# ProPrj_Rak11310v3b_2025-04-18.net
KiCad netlist of a schematic drawn in EasyEDA Pro
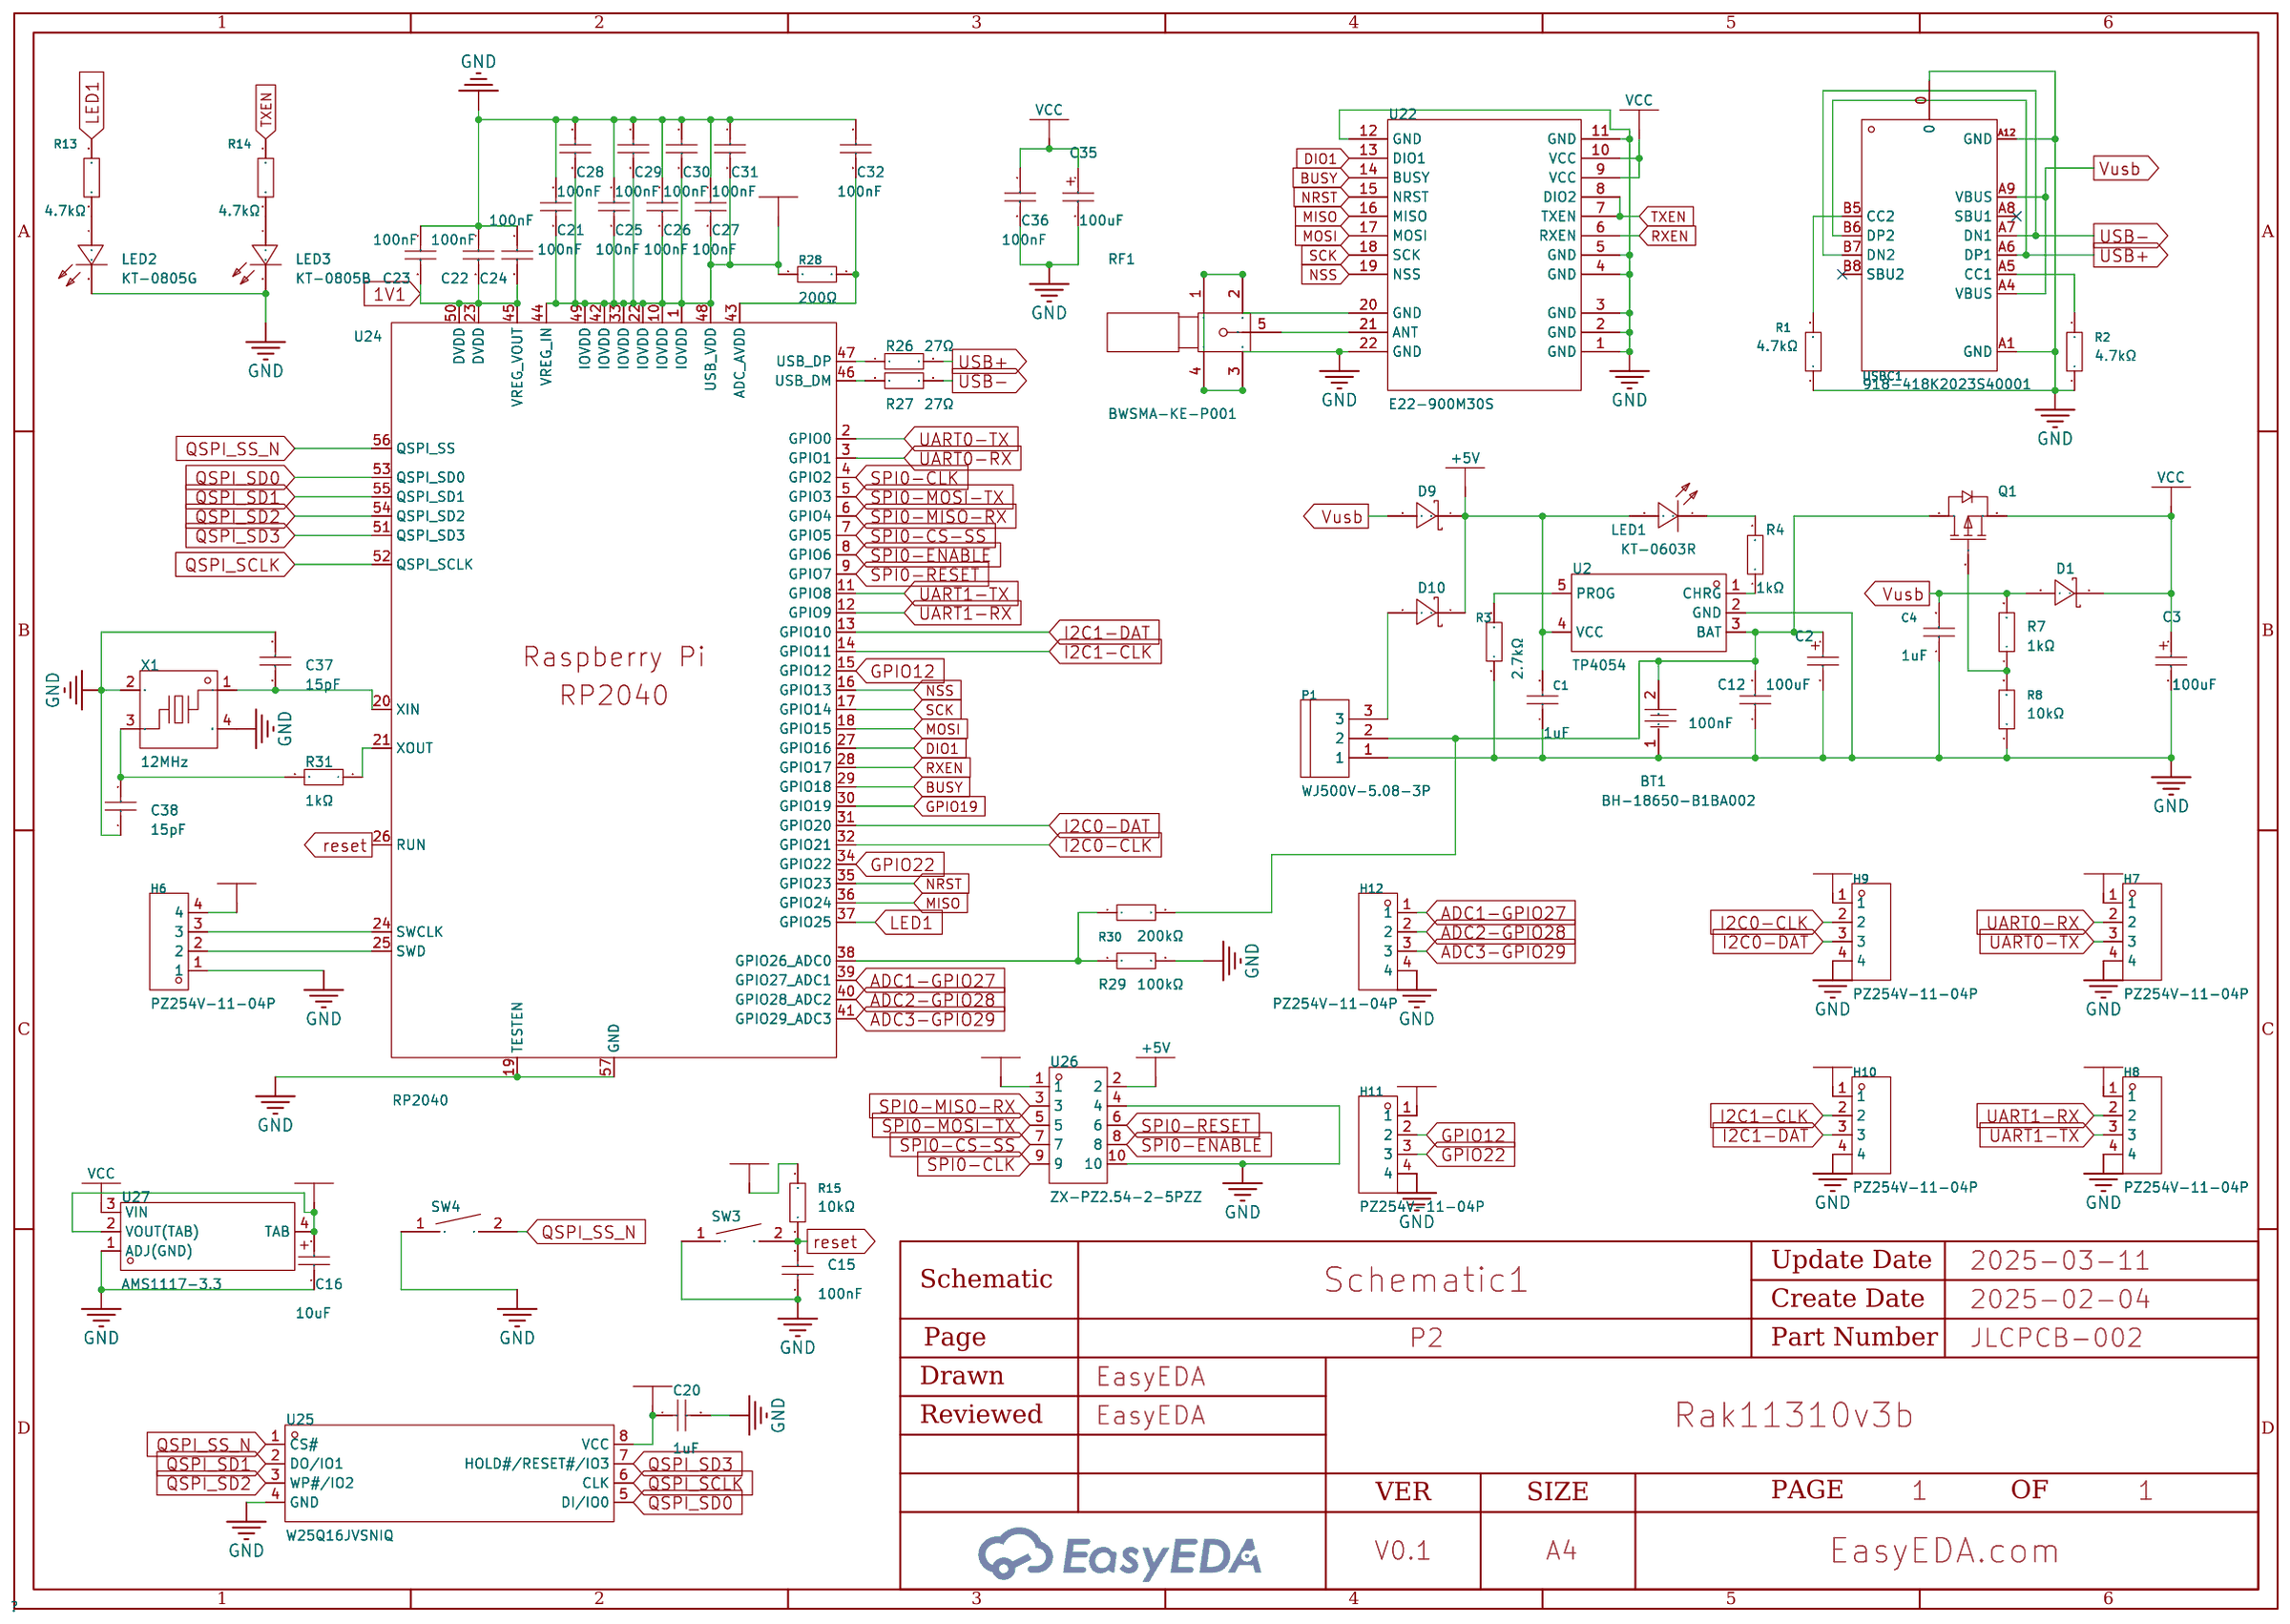
[diagram p0: schematic sheet]

(export (version "E")
  (design (tool "Eeschema 10.0.6"))
  (components
    (comp (ref "BT1")
      (value "BH-18650-B1BA002")
      (footprint "easyedapro:BATTERY-SMD_18650-1S-L77.1-W20.7-1")
      (description "Connector Type:Battery case Battery Type:18650")
      (fields (field (name "Manufacturer") "MYOUNG(美阳)"))
      (libsource (lib "easyedapro") (part "BH-18650-B1BA002"))
    )
    (comp (ref "C1")
      (value "1uF")
      (footprint "easyedapro:C0805")
      (fields
        (field (name "Manufacturer Part") "CL21B105KBFNNNE")
        (field (name "Manufacturer") "SAMSUNG(三星)")
      )
      (libsource (lib "easyedapro") (part "CL21B105KBFNNNE"))
    )
    (comp (ref "C2")
      (value "100uF")
      (footprint "easyedapro:CASE-B_3528")
      (fields (field (name "Manufacturer Part") "TAJB107K006RNJ") (field (name "Manufacturer") "Kyocera AVX"))
      (libsource (lib "easyedapro") (part "TAJB107K006RNJ"))
    )
    (comp (ref "C3")
      (value "100uF")
      (footprint "easyedapro:CASE-B_3528")
      (fields (field (name "Manufacturer Part") "TAJB107K006RNJ") (field (name "Manufacturer") "Kyocera AVX"))
      (libsource (lib "easyedapro") (part "TAJB107K006RNJ"))
    )
    (comp (ref "C4")
      (value "1uF")
      (footprint "easyedapro:C0805")
      (fields
        (field (name "Manufacturer Part") "CL21B105KBFNNNE")
        (field (name "Manufacturer") "SAMSUNG(三星)")
      )
      (libsource (lib "easyedapro") (part "CL21B105KBFNNNE"))
    )
    (comp (ref "C12")
      (value "100nF")
      (footprint "easyedapro:C0805")
      (fields
        (field (name "Manufacturer Part") "CC0805KRX7R9BB104")
        (field (name "Manufacturer") "YAGEO(国巨)")
      )
      (libsource (lib "easyedapro") (part "CC0805KRX7R9BB104"))
    )
    (comp (ref "C15")
      (value "100nF")
      (footprint "easyedapro:C0805")
      (fields
        (field (name "Manufacturer Part") "CC0805KRX7R9BB104")
        (field (name "Manufacturer") "YAGEO(国巨)")
      )
      (libsource (lib "easyedapro") (part "CC0805KRX7R9BB104"))
    )
    (comp (ref "C16")
      (value "10uF")
      (footprint "easyedapro:CAP-SMD_L3.2-W1.6-RD-C7171")
      (fields (field (name "Manufacturer Part") "TAJA106K016RNJ") (field (name "Manufacturer") "Kyocera AVX"))
      (libsource (lib "easyedapro") (part "TAJA106K016RNJ"))
    )
    (comp (ref "C20")
      (value "1uF")
      (footprint "easyedapro:C0603")
      (fields
        (field (name "Manufacturer Part") "CL10A105KO8NNNC")
        (field (name "Manufacturer") "SAMSUNG(三星)")
      )
      (libsource (lib "easyedapro") (part "CL10A105KO8NNNC"))
    )
    (comp (ref "C21")
      (value "100nF")
      (footprint "easyedapro:C0805")
      (fields
        (field (name "Manufacturer Part") "CC0805KRX7R9BB104")
        (field (name "Manufacturer") "YAGEO(国巨)")
      )
      (libsource (lib "easyedapro") (part "CC0805KRX7R9BB104"))
    )
    (comp (ref "C22")
      (value "100nF")
      (footprint "easyedapro:C0805")
      (fields
        (field (name "Manufacturer Part") "CC0805KRX7R9BB104")
        (field (name "Manufacturer") "YAGEO(国巨)")
      )
      (libsource (lib "easyedapro") (part "CC0805KRX7R9BB104"))
    )
    (comp (ref "C23")
      (value "100nF")
      (footprint "easyedapro:C0805")
      (fields
        (field (name "Manufacturer Part") "CC0805KRX7R9BB104")
        (field (name "Manufacturer") "YAGEO(国巨)")
      )
      (libsource (lib "easyedapro") (part "CC0805KRX7R9BB104"))
    )
    (comp (ref "C24")
      (value "100nF")
      (footprint "easyedapro:C0805")
      (fields
        (field (name "Manufacturer Part") "CC0805KRX7R9BB104")
        (field (name "Manufacturer") "YAGEO(国巨)")
      )
      (libsource (lib "easyedapro") (part "CC0805KRX7R9BB104"))
    )
    (comp (ref "C25")
      (value "100nF")
      (footprint "easyedapro:C0805")
      (fields
        (field (name "Manufacturer Part") "CC0805KRX7R9BB104")
        (field (name "Manufacturer") "YAGEO(国巨)")
      )
      (libsource (lib "easyedapro") (part "CC0805KRX7R9BB104"))
    )
    (comp (ref "C26")
      (value "100nF")
      (footprint "easyedapro:C0805")
      (fields
        (field (name "Manufacturer Part") "CC0805KRX7R9BB104")
        (field (name "Manufacturer") "YAGEO(国巨)")
      )
      (libsource (lib "easyedapro") (part "CC0805KRX7R9BB104"))
    )
    (comp (ref "C27")
      (value "100nF")
      (footprint "easyedapro:C0805")
      (fields
        (field (name "Manufacturer Part") "CC0805KRX7R9BB104")
        (field (name "Manufacturer") "YAGEO(国巨)")
      )
      (libsource (lib "easyedapro") (part "CC0805KRX7R9BB104"))
    )
    (comp (ref "C28")
      (value "100nF")
      (footprint "easyedapro:C0805")
      (fields
        (field (name "Manufacturer Part") "CC0805KRX7R9BB104")
        (field (name "Manufacturer") "YAGEO(国巨)")
      )
      (libsource (lib "easyedapro") (part "CC0805KRX7R9BB104"))
    )
    (comp (ref "C29")
      (value "100nF")
      (footprint "easyedapro:C0805")
      (fields
        (field (name "Manufacturer Part") "CC0805KRX7R9BB104")
        (field (name "Manufacturer") "YAGEO(国巨)")
      )
      (libsource (lib "easyedapro") (part "CC0805KRX7R9BB104"))
    )
    (comp (ref "C30")
      (value "100nF")
      (footprint "easyedapro:C0805")
      (fields
        (field (name "Manufacturer Part") "CC0805KRX7R9BB104")
        (field (name "Manufacturer") "YAGEO(国巨)")
      )
      (libsource (lib "easyedapro") (part "CC0805KRX7R9BB104"))
    )
    (comp (ref "C31")
      (value "100nF")
      (footprint "easyedapro:C0805")
      (fields
        (field (name "Manufacturer Part") "CC0805KRX7R9BB104")
        (field (name "Manufacturer") "YAGEO(国巨)")
      )
      (libsource (lib "easyedapro") (part "CC0805KRX7R9BB104"))
    )
    (comp (ref "C32")
      (value "100nF")
      (footprint "easyedapro:C0805")
      (fields
        (field (name "Manufacturer Part") "CC0805KRX7R9BB104")
        (field (name "Manufacturer") "YAGEO(国巨)")
      )
      (libsource (lib "easyedapro") (part "CC0805KRX7R9BB104"))
    )
    (comp (ref "C35")
      (value "100uF")
      (footprint "easyedapro:CASE-B_3528")
      (fields (field (name "Manufacturer Part") "TAJB107K006RNJ") (field (name "Manufacturer") "Kyocera AVX"))
      (libsource (lib "easyedapro") (part "TAJB107K006RNJ"))
    )
    (comp (ref "C36")
      (value "100nF")
      (footprint "easyedapro:C0805")
      (fields
        (field (name "Manufacturer Part") "CC0805KRX7R9BB104")
        (field (name "Manufacturer") "YAGEO(国巨)")
      )
      (libsource (lib "easyedapro") (part "CC0805KRX7R9BB104"))
    )
    (comp (ref "C37")
      (value "15pF")
      (footprint "easyedapro:C0603")
      (fields
        (field (name "Manufacturer Part") "CL10C150JB8NNNC")
        (field (name "Manufacturer") "SAMSUNG(三星)")
      )
      (libsource (lib "easyedapro") (part "CL10C150JB8NNNC"))
    )
    (comp (ref "C38")
      (value "15pF")
      (footprint "easyedapro:C0603")
      (fields
        (field (name "Manufacturer Part") "CL10C150JB8NNNC")
        (field (name "Manufacturer") "SAMSUNG(三星)")
      )
      (libsource (lib "easyedapro") (part "CL10C150JB8NNNC"))
    )
    (comp (ref "D1")
      (value "MBR140SFT1G")
      (footprint "easyedapro:SOD-123F_L2.8-W1.8-LS3.7-RD")
      (fields (field (name "Manufacturer") "onsemi(安森美)"))
      (libsource (lib "easyedapro") (part "MBR140SFT1G"))
    )
    (comp (ref "D9")
      (value "MBR140SFT1G")
      (footprint "easyedapro:SOD-123F_L2.8-W1.8-LS3.7-RD")
      (fields (field (name "Manufacturer") "onsemi(安森美)"))
      (libsource (lib "easyedapro") (part "MBR140SFT1G"))
    )
    (comp (ref "D10")
      (value "MBR140SFT1G")
      (footprint "easyedapro:SOD-123F_L2.8-W1.8-LS3.7-RD")
      (fields (field (name "Manufacturer") "onsemi(安森美)"))
      (libsource (lib "easyedapro") (part "MBR140SFT1G"))
    )
    (comp (ref "H6")
      (value "PZ254V-11-04P")
      (footprint "easyedapro:HDR-TH_4P-P2.54-V-M")
      (fields (field (name "Manufacturer") "XFCN(兴飞)"))
      (libsource (lib "easyedapro") (part "PZ254V-11-04P_C2691448"))
    )
    (comp (ref "H7")
      (value "PZ254V-11-04P")
      (footprint "easyedapro:HDR-TH_4P-P2.54-V-M")
      (fields (field (name "Manufacturer") "XFCN(兴飞)"))
      (libsource (lib "easyedapro") (part "PZ254V-11-04P_C2691448"))
    )
    (comp (ref "H8")
      (value "PZ254V-11-04P")
      (footprint "easyedapro:HDR-TH_4P-P2.54-V-M")
      (fields (field (name "Manufacturer") "XFCN(兴飞)"))
      (libsource (lib "easyedapro") (part "PZ254V-11-04P_C2691448"))
    )
    (comp (ref "H9")
      (value "PZ254V-11-04P")
      (footprint "easyedapro:HDR-TH_4P-P2.54-V-M")
      (fields (field (name "Manufacturer") "XFCN(兴飞)"))
      (libsource (lib "easyedapro") (part "PZ254V-11-04P_C2691448"))
    )
    (comp (ref "H10")
      (value "PZ254V-11-04P")
      (footprint "easyedapro:HDR-TH_4P-P2.54-V-M")
      (fields (field (name "Manufacturer") "XFCN(兴飞)"))
      (libsource (lib "easyedapro") (part "PZ254V-11-04P_C2691448"))
    )
    (comp (ref "H11")
      (value "PZ254V-11-04P")
      (footprint "easyedapro:HDR-TH_4P-P2.54-V-M")
      (fields (field (name "Manufacturer") "XFCN(兴飞)"))
      (libsource (lib "easyedapro") (part "PZ254V-11-04P_C2691448"))
    )
    (comp (ref "H12")
      (value "PZ254V-11-04P")
      (footprint "easyedapro:HDR-TH_4P-P2.54-V-M")
      (fields (field (name "Manufacturer") "XFCN(兴飞)"))
      (libsource (lib "easyedapro") (part "PZ254V-11-04P_C2691448"))
    )
    (comp (ref "LED1")
      (value "KT-0603R")
      (footprint "easyedapro:LED0603-RD")
      (fields (field (name "Manufacturer") "KENTO"))
      (libsource (lib "easyedapro") (part "KT-0603R"))
    )
    (comp (ref "LED2")
      (value "KT-0805G")
      (footprint "easyedapro:LED0805-R-RD")
      (fields (field (name "Manufacturer") "KENTO"))
      (libsource (lib "easyedapro") (part "0805G (Green)"))
    )
    (comp (ref "LED3")
      (value "KT-0805B")
      (footprint "easyedapro:LED0805-R-RD")
      (fields (field (name "Manufacturer") "KENTO"))
      (libsource (lib "easyedapro") (part "XL-0805QBC"))
    )
    (comp (ref "P1")
      (value "WJ500V-5.08-3P")
      (footprint "easyedapro:CONN-TH_3P-P5.00_WJ500V-5.08-3P")
      (fields (field (name "Manufacturer") "KANGNEX(康奈克斯电气)"))
      (libsource (lib "easyedapro") (part "WJ500V-5.08-3P-14-00A"))
    )
    (comp (ref "Q1")
      (value "AO3401A")
      (footprint "easyedapro:SOT-23_L2.9-W1.3-P1.90-LS2.4-BR")
      (fields (field (name "Manufacturer") "AOS"))
      (libsource (lib "easyedapro") (part "AO3401A"))
    )
    (comp (ref "R1")
      (value "4.7kΩ")
      (footprint "easyedapro:R0805")
      (fields
        (field (name "Manufacturer Part") "0805W8F4701T5E")
        (field (name "Manufacturer") "UNI-ROYAL(厚声)")
      )
      (libsource (lib "easyedapro") (part "0805W8F4701T5E"))
    )
    (comp (ref "R2")
      (value "4.7kΩ")
      (footprint "easyedapro:R0805")
      (fields
        (field (name "Manufacturer Part") "0805W8F4701T5E")
        (field (name "Manufacturer") "UNI-ROYAL(厚声)")
      )
      (libsource (lib "easyedapro") (part "0805W8F4701T5E"))
    )
    (comp (ref "R3")
      (value "2.7kΩ")
      (footprint "easyedapro:R0805")
      (fields
        (field (name "Manufacturer Part") "0805W8F2701T5E")
        (field (name "Manufacturer") "UNI-ROYAL(厚声)")
      )
      (libsource (lib "easyedapro") (part "0805W8F2701T5E"))
    )
    (comp (ref "R4")
      (value "1kΩ")
      (footprint "easyedapro:R0805")
      (fields
        (field (name "Manufacturer Part") "0805W8F1001T5E")
        (field (name "Manufacturer") "UNI-ROYAL(厚声)")
      )
      (libsource (lib "easyedapro") (part "0805W8F1001T5E"))
    )
    (comp (ref "R7")
      (value "1kΩ")
      (footprint "easyedapro:R0805")
      (fields
        (field (name "Manufacturer Part") "0805W8F1001T5E")
        (field (name "Manufacturer") "UNI-ROYAL(厚声)")
      )
      (libsource (lib "easyedapro") (part "0805W8F1001T5E"))
    )
    (comp (ref "R8")
      (value "10kΩ")
      (footprint "easyedapro:R0805")
      (fields
        (field (name "Manufacturer Part") "0805W8F1002T5E")
        (field (name "Manufacturer") "UNI-ROYAL(厚声)")
      )
      (libsource (lib "easyedapro") (part "0805W8F1002T5E"))
    )
    (comp (ref "R13")
      (value "4.7kΩ")
      (footprint "easyedapro:R0805")
      (fields
        (field (name "Manufacturer Part") "0805W8F4701T5E")
        (field (name "Manufacturer") "UNI-ROYAL(厚声)")
      )
      (libsource (lib "easyedapro") (part "0805W8F4701T5E"))
    )
    (comp (ref "R14")
      (value "4.7kΩ")
      (footprint "easyedapro:R0805")
      (fields
        (field (name "Manufacturer Part") "0805W8F4701T5E")
        (field (name "Manufacturer") "UNI-ROYAL(厚声)")
      )
      (libsource (lib "easyedapro") (part "0805W8F4701T5E"))
    )
    (comp (ref "R15")
      (value "10kΩ")
      (footprint "easyedapro:R0805")
      (fields
        (field (name "Manufacturer Part") "0805W8F1002T5E")
        (field (name "Manufacturer") "UNI-ROYAL(厚声)")
      )
      (libsource (lib "easyedapro") (part "0805W8F1002T5E"))
    )
    (comp (ref "R26")
      (value "27Ω")
      (footprint "easyedapro:R0603")
      (fields
        (field (name "Manufacturer Part") "0603WAF270JT5E")
        (field (name "Manufacturer") "UNI-ROYAL(厚声)")
      )
      (libsource (lib "easyedapro") (part "0603WAF270JT5E"))
    )
    (comp (ref "R27")
      (value "27Ω")
      (footprint "easyedapro:R0603")
      (fields
        (field (name "Manufacturer Part") "0603WAF270JT5E")
        (field (name "Manufacturer") "UNI-ROYAL(厚声)")
      )
      (libsource (lib "easyedapro") (part "0603WAF270JT5E"))
    )
    (comp (ref "R28")
      (value "200Ω")
      (footprint "easyedapro:R0603")
      (fields
        (field (name "Manufacturer Part") "0603WAF2000T5E")
        (field (name "Manufacturer") "UNI-ROYAL(厚声)")
      )
      (libsource (lib "easyedapro") (part "0603WAF2000T5E"))
    )
    (comp (ref "R29")
      (value "100kΩ")
      (footprint "easyedapro:R0603")
      (fields
        (field (name "Manufacturer Part") "0603WAF1003T5E")
        (field (name "Manufacturer") "UNI-ROYAL(厚声)")
      )
      (libsource (lib "easyedapro") (part "0603WAF1003T5E"))
    )
    (comp (ref "R30")
      (value "200kΩ")
      (footprint "easyedapro:R0603")
      (fields
        (field (name "Manufacturer Part") "0603WAF2003T5E")
        (field (name "Manufacturer") "UNI-ROYAL(厚声)")
      )
      (libsource (lib "easyedapro") (part "0603WAF2003T5E"))
    )
    (comp (ref "R31")
      (value "1kΩ")
      (footprint "easyedapro:R0805")
      (fields
        (field (name "Manufacturer Part") "0805W8F1001T5E")
        (field (name "Manufacturer") "UNI-ROYAL(厚声)")
      )
      (libsource (lib "easyedapro") (part "0805W8F1001T5E"))
    )
    (comp (ref "RF1")
      (value "BWSMA-KE-P001")
      (footprint "easyedapro:SMA-SMD_BWSMA-KE-P001")
      (fields (field (name "Manufacturer") "BAT WIRELESS(蝙蝠无线)"))
      (libsource (lib "easyedapro") (part "BWSMA-KE-P001"))
    )
    (comp (ref "SW3")
      (value "TSA343G00D-250J2")
      (footprint "easyedapro:SW-SMD_L4.0-W2.9-P4.15-EH")
      (fields (field (name "Manufacturer") "BRIGHT(博瑞泰)"))
      (libsource (lib "easyedapro") (part "TSA343G00D-250J2"))
    )
    (comp (ref "SW4")
      (value "TSA343G00D-250J2")
      (footprint "easyedapro:SW-SMD_L4.0-W2.9-P4.15-EH")
      (fields (field (name "Manufacturer") "BRIGHT(博瑞泰)"))
      (libsource (lib "easyedapro") (part "TSA343G00D-250J2"))
    )
    (comp (ref "U2")
      (value "TP4054")
      (footprint "easyedapro:SOT-23-5_L2.9-W1.6-P0.95-LS2.8-BR")
      (fields (field (name "Manufacturer") "JSMSEMI(杰盛微)"))
      (libsource (lib "easyedapro") (part "TP4054_C5381776"))
    )
    (comp (ref "U22")
      (value "E22-900M30S")
      (footprint "easyedapro:WIRELM-SMD_E22-900M30S")
      (fields (field (name "Manufacturer") "EBYTE(亿佰特)"))
      (libsource (lib "easyedapro") (part "E22-900M30S"))
    )
    (comp (ref "U24")
      (value "RP2040")
      (footprint "easyedapro:LQFN-56_L7.0-W7.0-P0.4-EP")
      (fields (field (name "Manufacturer") "Raspberry Pi(树莓派)"))
      (libsource (lib "easyedapro") (part "RP2040"))
    )
    (comp (ref "U25")
      (value "W25Q16JVSNIQ")
      (footprint "easyedapro:SOP-8_L4.9-W3.9-P1.27-LS6.0-BL")
      (fields (field (name "Manufacturer") "WINBOND(华邦)"))
      (libsource (lib "easyedapro") (part "W25Q16JVSNIQ TR"))
    )
    (comp (ref "U26")
      (value "ZX-PZ2.54-2-5PZZ")
      (footprint "easyedapro:HDR-TH_10P-P2.54-V-M-R2-C5-S2.54")
      (fields (field (name "Manufacturer") "Megastar(兆星)"))
      (libsource (lib "easyedapro") (part "ZX-PZ2.54-2-5PZZ"))
    )
    (comp (ref "U27")
      (value "AMS1117-3.3")
      (footprint "easyedapro:SOT-223-4_L6.5-W3.5-P2.30-LS7.0-BR")
      (fields (field (name "Manufacturer") "UMW(友台半导体)"))
      (libsource (lib "easyedapro") (part "AMS1117-3.3_C347222"))
    )
    (comp (ref "USBC1")
      (value "918-418K2023S40001")
      (footprint "easyedapro:USB-C-SMD_TYPE-C-USB-17")
      (fields (field (name "Manufacturer") "精拓金"))
      (libsource (lib "easyedapro") (part "USB3.1C16PFSMT"))
    )
    (comp (ref "X1")
      (value "12MHz")
      (footprint "easyedapro:OSC-SMD_4P-L3.2-W2.5-BL")
      (fields
        (field (name "Manufacturer Part") "XL2EL89COI-111YLC-12M")
        (field (name "Manufacturer") "YXC(扬兴晶振)")
      )
      (libsource (lib "easyedapro") (part "XL2EL89COI-111YLC-12M"))
    )
  )
  (nets
    (net (code "1") (name "+5V") (class "Default")
      (node (ref "C1") (pin "2") (pinfunction "2_2") (pintype "input"))
      (node (ref "D10") (pin "1") (pinfunction "K_1") (pintype "unspecified"))
      (node (ref "D9") (pin "1") (pinfunction "K_1") (pintype "unspecified"))
      (node (ref "LED1") (pin "2") (pinfunction "A_2") (pintype "input"))
      (node (ref "U2") (pin "4") (pinfunction "VCC_4") (pintype "unspecified"))
      (node (ref "U26") (pin "2") (pinfunction "2_2") (pintype "unspecified"))
    )
    (net (code "2") (name "1V1") (class "Default")
      (node (ref "C22") (pin "2") (pinfunction "2_2") (pintype "input"))
      (node (ref "C23") (pin "2") (pinfunction "2_2") (pintype "input"))
      (node (ref "C24") (pin "2") (pinfunction "2_2") (pintype "input"))
      (node (ref "U24") (pin "23") (pinfunction "DVDD_23") (pintype "bidirectional"))
      (node (ref "U24") (pin "45") (pinfunction "VREG_VOUT_45") (pintype "bidirectional"))
      (node (ref "U24") (pin "50") (pinfunction "DVDD_50") (pintype "bidirectional"))
    )
    (net (code "3") (name "3.3V") (class "Default")
      (node (ref "C16") (pin "1") (pinfunction "1_1") (pintype "input"))
      (node (ref "C20") (pin "1") (pinfunction "1_1") (pintype "input"))
      (node (ref "C21") (pin "2") (pinfunction "2_2") (pintype "input"))
      (node (ref "C25") (pin "2") (pinfunction "2_2") (pintype "input"))
      (node (ref "C26") (pin "2") (pinfunction "2_2") (pintype "input"))
      (node (ref "C27") (pin "2") (pinfunction "2_2") (pintype "input"))
      (node (ref "C28") (pin "2") (pinfunction "2_2") (pintype "input"))
      (node (ref "C29") (pin "2") (pinfunction "2_2") (pintype "input"))
      (node (ref "C30") (pin "2") (pinfunction "2_2") (pintype "input"))
      (node (ref "C31") (pin "2") (pinfunction "2_2") (pintype "input"))
      (node (ref "H10") (pin "1") (pinfunction "1_1") (pintype "input"))
      (node (ref "H11") (pin "1") (pinfunction "1_1") (pintype "input"))
      (node (ref "H6") (pin "4") (pinfunction "4_4") (pintype "input"))
      (node (ref "H7") (pin "1") (pinfunction "1_1") (pintype "input"))
      (node (ref "H8") (pin "1") (pinfunction "1_1") (pintype "input"))
      (node (ref "H9") (pin "1") (pinfunction "1_1") (pintype "input"))
      (node (ref "R15") (pin "2") (pinfunction "2_2") (pintype "input"))
      (node (ref "R28") (pin "1") (pinfunction "1_1") (pintype "input"))
      (node (ref "U24") (pin "1") (pinfunction "IOVDD_1") (pintype "bidirectional"))
      (node (ref "U24") (pin "10") (pinfunction "IOVDD_10") (pintype "bidirectional"))
      (node (ref "U24") (pin "22") (pinfunction "IOVDD_22") (pintype "bidirectional"))
      (node (ref "U24") (pin "33") (pinfunction "IOVDD_33") (pintype "bidirectional"))
      (node (ref "U24") (pin "42") (pinfunction "IOVDD_42") (pintype "bidirectional"))
      (node (ref "U24") (pin "44") (pinfunction "VREG_IN_44") (pintype "bidirectional"))
      (node (ref "U24") (pin "48") (pinfunction "USB_VDD_48") (pintype "bidirectional"))
      (node (ref "U24") (pin "49") (pinfunction "IOVDD_49") (pintype "bidirectional"))
      (node (ref "U25") (pin "8") (pinfunction "VCC_8") (pintype "unspecified"))
      (node (ref "U26") (pin "1") (pinfunction "1_1") (pintype "unspecified"))
      (node (ref "U27") (pin "2") (pinfunction "VOUT(TAB)_2") (pintype "unspecified"))
      (node (ref "U27") (pin "4") (pinfunction "TAB_4") (pintype "unspecified"))
    )
    (net (code "4") (name "ADC1-GPIO27") (class "Default")
      (node (ref "H12") (pin "1") (pinfunction "1_1") (pintype "input"))
      (node (ref "U24") (pin "39") (pinfunction "GPIO27_ADC1_39") (pintype "bidirectional"))
    )
    (net (code "5") (name "ADC2-GPIO28") (class "Default")
      (node (ref "H12") (pin "2") (pinfunction "2_2") (pintype "input"))
      (node (ref "U24") (pin "40") (pinfunction "GPIO28_ADC2_40") (pintype "bidirectional"))
    )
    (net (code "6") (name "ADC3-GPIO29") (class "Default")
      (node (ref "H12") (pin "3") (pinfunction "3_3") (pintype "input"))
      (node (ref "U24") (pin "41") (pinfunction "GPIO29_ADC3_41") (pintype "bidirectional"))
    )
    (net (code "7") (name "BUSY") (class "Default")
      (node (ref "U22") (pin "14") (pinfunction "BUSY_14") (pintype "unspecified"))
      (node (ref "U24") (pin "29") (pinfunction "GPIO18_29") (pintype "bidirectional"))
    )
    (net (code "8") (name "DIO1") (class "Default")
      (node (ref "U22") (pin "13") (pinfunction "DIO1_13") (pintype "unspecified"))
      (node (ref "U24") (pin "27") (pinfunction "GPIO16_27") (pintype "bidirectional"))
    )
    (net (code "9") (name "GND") (class "Default")
      (node (ref "BT1") (pin "1") (pinfunction "1_1") (pintype "input"))
      (node (ref "C1") (pin "1") (pinfunction "1_1") (pintype "input"))
      (node (ref "C12") (pin "1") (pinfunction "1_1") (pintype "input"))
      (node (ref "C15") (pin "1") (pinfunction "1_1") (pintype "input"))
      (node (ref "C16") (pin "2") (pinfunction "2_2") (pintype "input"))
      (node (ref "C2") (pin "2") (pinfunction "2_2") (pintype "input"))
      (node (ref "C20") (pin "2") (pinfunction "2_2") (pintype "input"))
      (node (ref "C21") (pin "1") (pinfunction "1_1") (pintype "input"))
      (node (ref "C22") (pin "1") (pinfunction "1_1") (pintype "input"))
      (node (ref "C23") (pin "1") (pinfunction "1_1") (pintype "input"))
      (node (ref "C24") (pin "1") (pinfunction "1_1") (pintype "input"))
      (node (ref "C25") (pin "1") (pinfunction "1_1") (pintype "input"))
      (node (ref "C26") (pin "1") (pinfunction "1_1") (pintype "input"))
      (node (ref "C27") (pin "1") (pinfunction "1_1") (pintype "input"))
      (node (ref "C28") (pin "1") (pinfunction "1_1") (pintype "input"))
      (node (ref "C29") (pin "1") (pinfunction "1_1") (pintype "input"))
      (node (ref "C3") (pin "2") (pinfunction "2_2") (pintype "input"))
      (node (ref "C30") (pin "1") (pinfunction "1_1") (pintype "input"))
      (node (ref "C31") (pin "1") (pinfunction "1_1") (pintype "input"))
      (node (ref "C32") (pin "1") (pinfunction "1_1") (pintype "input"))
      (node (ref "C35") (pin "2") (pinfunction "2_2") (pintype "input"))
      (node (ref "C36") (pin "2") (pinfunction "2_2") (pintype "input"))
      (node (ref "C37") (pin "2") (pinfunction "2_2") (pintype "input"))
      (node (ref "C38") (pin "1") (pinfunction "1_1") (pintype "input"))
      (node (ref "C4") (pin "1") (pinfunction "1_1") (pintype "input"))
      (node (ref "H10") (pin "4") (pinfunction "4_4") (pintype "input"))
      (node (ref "H11") (pin "4") (pinfunction "4_4") (pintype "input"))
      (node (ref "H12") (pin "4") (pinfunction "4_4") (pintype "input"))
      (node (ref "H6") (pin "1") (pinfunction "1_1") (pintype "input"))
      (node (ref "H7") (pin "4") (pinfunction "4_4") (pintype "input"))
      (node (ref "H8") (pin "4") (pinfunction "4_4") (pintype "input"))
      (node (ref "H9") (pin "4") (pinfunction "4_4") (pintype "input"))
      (node (ref "LED2") (pin "2") (pinfunction "K_2") (pintype "unspecified"))
      (node (ref "LED3") (pin "2") (pinfunction "K_2") (pintype "unspecified"))
      (node (ref "P1") (pin "1") (pinfunction "1_1") (pintype "input"))
      (node (ref "R1") (pin "1") (pinfunction "1_1") (pintype "input"))
      (node (ref "R2") (pin "1") (pinfunction "1_1") (pintype "input"))
      (node (ref "R29") (pin "2") (pinfunction "2_2") (pintype "input"))
      (node (ref "R3") (pin "1") (pinfunction "1_1") (pintype "input"))
      (node (ref "R8") (pin "1") (pinfunction "1_1") (pintype "input"))
      (node (ref "RF1") (pin "1") (pinfunction "1_1") (pintype "unspecified"))
      (node (ref "RF1") (pin "2") (pinfunction "2_2") (pintype "unspecified"))
      (node (ref "RF1") (pin "3") (pinfunction "3_3") (pintype "unspecified"))
      (node (ref "RF1") (pin "4") (pinfunction "4_4") (pintype "unspecified"))
      (node (ref "SW3") (pin "1") (pinfunction "1_1") (pintype "input"))
      (node (ref "SW4") (pin "1") (pinfunction "1_1") (pintype "input"))
      (node (ref "U2") (pin "2") (pinfunction "GND_2") (pintype "unspecified"))
      (node (ref "U22") (pin "1") (pinfunction "GND_1") (pintype "unspecified"))
      (node (ref "U22") (pin "11") (pinfunction "GND_11") (pintype "unspecified"))
      (node (ref "U22") (pin "12") (pinfunction "GND_12") (pintype "unspecified"))
      (node (ref "U22") (pin "2") (pinfunction "GND_2") (pintype "unspecified"))
      (node (ref "U22") (pin "20") (pinfunction "GND_20") (pintype "unspecified"))
      (node (ref "U22") (pin "22") (pinfunction "GND_22") (pintype "unspecified"))
      (node (ref "U22") (pin "3") (pinfunction "GND_3") (pintype "unspecified"))
      (node (ref "U22") (pin "4") (pinfunction "GND_4") (pintype "unspecified"))
      (node (ref "U22") (pin "5") (pinfunction "GND_5") (pintype "unspecified"))
      (node (ref "U24") (pin "19") (pinfunction "TESTEN_19") (pintype "unspecified"))
      (node (ref "U24") (pin "57") (pinfunction "GND_57") (pintype "bidirectional"))
      (node (ref "U25") (pin "4") (pinfunction "GND_4") (pintype "unspecified"))
      (node (ref "U26") (pin "10") (pinfunction "10_10") (pintype "unspecified"))
      (node (ref "U26") (pin "4") (pinfunction "4_4") (pintype "unspecified"))
      (node (ref "U27") (pin "1") (pinfunction "ADJ(GND)_1") (pintype "unspecified"))
      (node (ref "USBC1") (pin "0") (pinfunction "0_0") (pintype "input"))
      (node (ref "USBC1") (pin "A1") (pinfunction "GND_A1") (pintype "input"))
      (node (ref "USBC1") (pin "A12") (pinfunction "GND_A12") (pintype "input"))
      (node (ref "X1") (pin "2") (pinfunction "GND_2") (pintype "input"))
      (node (ref "X1") (pin "4") (pinfunction "GND_4") (pintype "input"))
    )
    (net (code "10") (name "GPIO12") (class "Default")
      (node (ref "H11") (pin "2") (pinfunction "2_2") (pintype "input"))
      (node (ref "U24") (pin "15") (pinfunction "GPIO12_15") (pintype "bidirectional"))
    )
    (net (code "11") (name "GPIO19") (class "Default")
      (node (ref "U24") (pin "30") (pinfunction "GPIO19_30") (pintype "bidirectional"))
    )
    (net (code "12") (name "GPIO22") (class "Default")
      (node (ref "H11") (pin "3") (pinfunction "3_3") (pintype "input"))
      (node (ref "U24") (pin "34") (pinfunction "GPIO22_34") (pintype "bidirectional"))
    )
    (net (code "13") (name "I2C0-CLK") (class "Default")
      (node (ref "H9") (pin "2") (pinfunction "2_2") (pintype "input"))
      (node (ref "U24") (pin "32") (pinfunction "GPIO21_32") (pintype "bidirectional"))
    )
    (net (code "14") (name "I2C0-DAT") (class "Default")
      (node (ref "H9") (pin "3") (pinfunction "3_3") (pintype "input"))
      (node (ref "U24") (pin "31") (pinfunction "GPIO20_31") (pintype "bidirectional"))
    )
    (net (code "15") (name "I2C1-CLK") (class "Default")
      (node (ref "H10") (pin "2") (pinfunction "2_2") (pintype "input"))
      (node (ref "U24") (pin "14") (pinfunction "GPIO11_14") (pintype "bidirectional"))
    )
    (net (code "16") (name "I2C1-DAT") (class "Default")
      (node (ref "H10") (pin "3") (pinfunction "3_3") (pintype "input"))
      (node (ref "U24") (pin "13") (pinfunction "GPIO10_13") (pintype "bidirectional"))
    )
    (net (code "17") (name "LED1") (class "Default")
      (node (ref "R13") (pin "2") (pinfunction "2_2") (pintype "input"))
      (node (ref "U24") (pin "37") (pinfunction "GPIO25_37") (pintype "bidirectional"))
    )
    (net (code "18") (name "MISO") (class "Default")
      (node (ref "U22") (pin "16") (pinfunction "MISO_16") (pintype "unspecified"))
      (node (ref "U24") (pin "36") (pinfunction "GPIO24_36") (pintype "bidirectional"))
    )
    (net (code "19") (name "MOSI") (class "Default")
      (node (ref "U22") (pin "17") (pinfunction "MOSI_17") (pintype "unspecified"))
      (node (ref "U24") (pin "18") (pinfunction "GPIO15_18") (pintype "bidirectional"))
    )
    (net (code "20") (name "NRST") (class "Default")
      (node (ref "U22") (pin "15") (pinfunction "NRST_15") (pintype "unspecified"))
      (node (ref "U24") (pin "35") (pinfunction "GPIO23_35") (pintype "bidirectional"))
    )
    (net (code "21") (name "NSS") (class "Default")
      (node (ref "U22") (pin "19") (pinfunction "NSS_19") (pintype "unspecified"))
      (node (ref "U24") (pin "16") (pinfunction "GPIO13_16") (pintype "bidirectional"))
    )
    (net (code "22") (name "Net-(C38-Pad2)") (class "Default")
      (node (ref "C38") (pin "2") (pinfunction "2_2") (pintype "input"))
      (node (ref "R31") (pin "2") (pinfunction "2_2") (pintype "input"))
      (node (ref "X1") (pin "3") (pinfunction "3_3") (pintype "input"))
    )
    (net (code "23") (name "Net-(D10-A)") (class "Default")
      (node (ref "D10") (pin "2") (pinfunction "A_2") (pintype "unspecified"))
      (node (ref "P1") (pin "3") (pinfunction "3_3") (pintype "input"))
    )
    (net (code "24") (name "Net-(LED1-K)") (class "Default")
      (node (ref "LED1") (pin "1") (pinfunction "K_1") (pintype "input"))
      (node (ref "R4") (pin "2") (pinfunction "2_2") (pintype "input"))
    )
    (net (code "25") (name "Net-(LED2-A)") (class "Default")
      (node (ref "LED2") (pin "1") (pinfunction "A_1") (pintype "unspecified"))
      (node (ref "R13") (pin "1") (pinfunction "1_1") (pintype "input"))
    )
    (net (code "26") (name "Net-(LED3-A)") (class "Default")
      (node (ref "LED3") (pin "1") (pinfunction "A_1") (pintype "unspecified"))
      (node (ref "R14") (pin "1") (pinfunction "1_1") (pintype "input"))
    )
    (net (code "27") (name "Net-(Q1-D)") (class "Default")
      (node (ref "BT1") (pin "2") (pinfunction "2_2") (pintype "input"))
      (node (ref "C12") (pin "2") (pinfunction "2_2") (pintype "input"))
      (node (ref "C2") (pin "1") (pinfunction "1_1") (pintype "input"))
      (node (ref "P1") (pin "2") (pinfunction "2_2") (pintype "input"))
      (node (ref "Q1") (pin "3") (pinfunction "D_3") (pintype "unspecified"))
      (node (ref "R30") (pin "2") (pinfunction "2_2") (pintype "input"))
      (node (ref "U2") (pin "3") (pinfunction "BAT_3") (pintype "unspecified"))
    )
    (net (code "28") (name "Net-(Q1-G)") (class "Default")
      (node (ref "Q1") (pin "1") (pinfunction "G_1") (pintype "unspecified"))
      (node (ref "R7") (pin "1") (pinfunction "1_1") (pintype "input"))
      (node (ref "R8") (pin "2") (pinfunction "2_2") (pintype "input"))
    )
    (net (code "29") (name "Net-(U2-CHRG)") (class "Default")
      (node (ref "R4") (pin "1") (pinfunction "1_1") (pintype "input"))
      (node (ref "U2") (pin "1") (pinfunction "CHRG_1") (pintype "unspecified"))
    )
    (net (code "30") (name "Net-(U2-PROG)") (class "Default")
      (node (ref "R3") (pin "2") (pinfunction "2_2") (pintype "input"))
      (node (ref "U2") (pin "5") (pinfunction "PROG_5") (pintype "unspecified"))
    )
    (net (code "31") (name "Net-(U22-ANT)") (class "Default")
      (node (ref "RF1") (pin "5") (pinfunction "5_5") (pintype "unspecified"))
      (node (ref "U22") (pin "21") (pinfunction "ANT_21") (pintype "unspecified"))
    )
    (net (code "32") (name "Net-(U24-ADC_AVDD)") (class "Default")
      (node (ref "C32") (pin "2") (pinfunction "2_2") (pintype "input"))
      (node (ref "R28") (pin "2") (pinfunction "2_2") (pintype "input"))
      (node (ref "U24") (pin "43") (pinfunction "ADC_AVDD_43") (pintype "bidirectional"))
    )
    (net (code "33") (name "Net-(U24-GPIO26_ADC0)") (class "Default")
      (node (ref "R29") (pin "1") (pinfunction "1_1") (pintype "input"))
      (node (ref "R30") (pin "1") (pinfunction "1_1") (pintype "input"))
      (node (ref "U24") (pin "38") (pinfunction "GPIO26_ADC0_38") (pintype "bidirectional"))
    )
    (net (code "34") (name "Net-(U24-SWCLK)") (class "Default")
      (node (ref "H6") (pin "3") (pinfunction "3_3") (pintype "input"))
      (node (ref "U24") (pin "24") (pinfunction "SWCLK_24") (pintype "output"))
    )
    (net (code "35") (name "Net-(U24-SWD)") (class "Default")
      (node (ref "H6") (pin "2") (pinfunction "2_2") (pintype "input"))
      (node (ref "U24") (pin "25") (pinfunction "SWD_25") (pintype "bidirectional"))
    )
    (net (code "36") (name "Net-(U24-USB_DM)") (class "Default")
      (node (ref "R27") (pin "1") (pinfunction "1_1") (pintype "input"))
      (node (ref "U24") (pin "46") (pinfunction "USB_DM_46") (pintype "bidirectional"))
    )
    (net (code "37") (name "Net-(U24-USB_DP)") (class "Default")
      (node (ref "R26") (pin "1") (pinfunction "1_1") (pintype "input"))
      (node (ref "U24") (pin "47") (pinfunction "USB_DP_47") (pintype "bidirectional"))
    )
    (net (code "38") (name "Net-(U24-XIN)") (class "Default")
      (node (ref "C37") (pin "1") (pinfunction "1_1") (pintype "input"))
      (node (ref "U24") (pin "20") (pinfunction "XIN_20") (pintype "input"))
      (node (ref "X1") (pin "1") (pinfunction "1_1") (pintype "input"))
    )
    (net (code "39") (name "Net-(U24-XOUT)") (class "Default")
      (node (ref "R31") (pin "1") (pinfunction "1_1") (pintype "input"))
      (node (ref "U24") (pin "21") (pinfunction "XOUT_21") (pintype "unspecified"))
    )
    (net (code "40") (name "Net-(USBC1-CC1)") (class "Default")
      (node (ref "R2") (pin "2") (pinfunction "2_2") (pintype "input"))
      (node (ref "USBC1") (pin "A5") (pinfunction "CC1_A5") (pintype "input"))
    )
    (net (code "41") (name "Net-(USBC1-CC2)") (class "Default")
      (node (ref "R1") (pin "2") (pinfunction "2_2") (pintype "input"))
      (node (ref "USBC1") (pin "B5") (pinfunction "CC2_B5") (pintype "input"))
    )
    (net (code "42") (name "QSPI_SCLK") (class "Default")
      (node (ref "U24") (pin "52") (pinfunction "QSPI_SCLK_52") (pintype "output"))
      (node (ref "U25") (pin "6") (pinfunction "CLK_6") (pintype "unspecified"))
    )
    (net (code "43") (name "QSPI_SD0") (class "Default")
      (node (ref "U24") (pin "53") (pinfunction "QSPI_SD0_53") (pintype "bidirectional"))
      (node (ref "U25") (pin "5") (pinfunction "DI/IO0_5") (pintype "unspecified"))
    )
    (net (code "44") (name "QSPI_SD1") (class "Default")
      (node (ref "U24") (pin "55") (pinfunction "QSPI_SD1_55") (pintype "bidirectional"))
      (node (ref "U25") (pin "2") (pinfunction "DO/IO1_2") (pintype "unspecified"))
    )
    (net (code "45") (name "QSPI_SD2") (class "Default")
      (node (ref "U24") (pin "54") (pinfunction "QSPI_SD2_54") (pintype "bidirectional"))
      (node (ref "U25") (pin "3") (pinfunction "WP#/IO2_3") (pintype "unspecified"))
    )
    (net (code "46") (name "QSPI_SD3") (class "Default")
      (node (ref "U24") (pin "51") (pinfunction "QSPI_SD3_51") (pintype "bidirectional"))
      (node (ref "U25") (pin "7") (pinfunction "HOLD#/RESET#/IO3_7") (pintype "unspecified"))
    )
    (net (code "47") (name "QSPI_SS_N") (class "Default")
      (node (ref "SW4") (pin "2") (pinfunction "2_2") (pintype "input"))
      (node (ref "U24") (pin "56") (pinfunction "QSPI_SS_56") (pintype "bidirectional"))
      (node (ref "U25") (pin "1") (pinfunction "CS#_1") (pintype "unspecified"))
    )
    (net (code "48") (name "RXEN") (class "Default")
      (node (ref "U22") (pin "6") (pinfunction "RXEN_6") (pintype "unspecified"))
      (node (ref "U24") (pin "28") (pinfunction "GPIO17_28") (pintype "bidirectional"))
    )
    (net (code "49") (name "SCK") (class "Default")
      (node (ref "U22") (pin "18") (pinfunction "SCK_18") (pintype "unspecified"))
      (node (ref "U24") (pin "17") (pinfunction "GPIO14_17") (pintype "bidirectional"))
    )
    (net (code "50") (name "SPI0-CLK") (class "Default")
      (node (ref "U24") (pin "4") (pinfunction "GPIO2_4") (pintype "bidirectional"))
      (node (ref "U26") (pin "9") (pinfunction "9_9") (pintype "unspecified"))
    )
    (net (code "51") (name "SPI0-CS-SS") (class "Default")
      (node (ref "U24") (pin "7") (pinfunction "GPIO5_7") (pintype "bidirectional"))
      (node (ref "U26") (pin "7") (pinfunction "7_7") (pintype "unspecified"))
    )
    (net (code "52") (name "SPI0-ENABLE") (class "Default")
      (node (ref "U24") (pin "8") (pinfunction "GPIO6_8") (pintype "bidirectional"))
      (node (ref "U26") (pin "8") (pinfunction "8_8") (pintype "unspecified"))
    )
    (net (code "53") (name "SPI0-MISO-RX") (class "Default")
      (node (ref "U24") (pin "6") (pinfunction "GPIO4_6") (pintype "bidirectional"))
      (node (ref "U26") (pin "3") (pinfunction "3_3") (pintype "unspecified"))
    )
    (net (code "54") (name "SPI0-MOSI-TX") (class "Default")
      (node (ref "U24") (pin "5") (pinfunction "GPIO3_5") (pintype "bidirectional"))
      (node (ref "U26") (pin "5") (pinfunction "5_5") (pintype "unspecified"))
    )
    (net (code "55") (name "SPI0-RESET") (class "Default")
      (node (ref "U24") (pin "9") (pinfunction "GPIO7_9") (pintype "bidirectional"))
      (node (ref "U26") (pin "6") (pinfunction "6_6") (pintype "unspecified"))
    )
    (net (code "56") (name "TXEN") (class "Default")
      (node (ref "R14") (pin "2") (pinfunction "2_2") (pintype "input"))
      (node (ref "U22") (pin "7") (pinfunction "TXEN_7") (pintype "unspecified"))
      (node (ref "U22") (pin "8") (pinfunction "DIO2_8") (pintype "unspecified"))
    )
    (net (code "57") (name "UART0-RX") (class "Default")
      (node (ref "H7") (pin "2") (pinfunction "2_2") (pintype "input"))
      (node (ref "U24") (pin "3") (pinfunction "GPIO1_3") (pintype "bidirectional"))
    )
    (net (code "58") (name "UART0-TX") (class "Default")
      (node (ref "H7") (pin "3") (pinfunction "3_3") (pintype "input"))
      (node (ref "U24") (pin "2") (pinfunction "GPIO0_2") (pintype "bidirectional"))
    )
    (net (code "59") (name "UART1-RX") (class "Default")
      (node (ref "H8") (pin "2") (pinfunction "2_2") (pintype "input"))
      (node (ref "U24") (pin "12") (pinfunction "GPIO9_12") (pintype "bidirectional"))
    )
    (net (code "60") (name "UART1-TX") (class "Default")
      (node (ref "H8") (pin "3") (pinfunction "3_3") (pintype "input"))
      (node (ref "U24") (pin "11") (pinfunction "GPIO8_11") (pintype "bidirectional"))
    )
    (net (code "61") (name "USB+") (class "Default")
      (node (ref "R26") (pin "2") (pinfunction "2_2") (pintype "input"))
      (node (ref "USBC1") (pin "A6") (pinfunction "DP1_A6") (pintype "input"))
      (node (ref "USBC1") (pin "B6") (pinfunction "DP2_B6") (pintype "input"))
    )
    (net (code "62") (name "USB-") (class "Default")
      (node (ref "R27") (pin "2") (pinfunction "2_2") (pintype "input"))
      (node (ref "USBC1") (pin "A7") (pinfunction "DN1_A7") (pintype "input"))
      (node (ref "USBC1") (pin "B7") (pinfunction "DN2_B7") (pintype "input"))
    )
    (net (code "63") (name "VCC") (class "Default")
      (node (ref "C3") (pin "1") (pinfunction "1_1") (pintype "input"))
      (node (ref "C35") (pin "1") (pinfunction "1_1") (pintype "input"))
      (node (ref "C36") (pin "1") (pinfunction "1_1") (pintype "input"))
      (node (ref "D1") (pin "1") (pinfunction "K_1") (pintype "unspecified"))
      (node (ref "Q1") (pin "2") (pinfunction "S_2") (pintype "unspecified"))
      (node (ref "U22") (pin "10") (pinfunction "VCC_10") (pintype "unspecified"))
      (node (ref "U22") (pin "9") (pinfunction "VCC_9") (pintype "unspecified"))
      (node (ref "U27") (pin "3") (pinfunction "VIN_3") (pintype "unspecified"))
    )
    (net (code "64") (name "Vusb") (class "Default")
      (node (ref "C4") (pin "2") (pinfunction "2_2") (pintype "input"))
      (node (ref "D1") (pin "2") (pinfunction "A_2") (pintype "unspecified"))
      (node (ref "D9") (pin "2") (pinfunction "A_2") (pintype "unspecified"))
      (node (ref "R7") (pin "2") (pinfunction "2_2") (pintype "input"))
      (node (ref "USBC1") (pin "A4") (pinfunction "VBUS_A4") (pintype "input"))
      (node (ref "USBC1") (pin "A9") (pinfunction "VBUS_A9") (pintype "input"))
    )
    (net (code "65") (name "reset") (class "Default")
      (node (ref "C15") (pin "2") (pinfunction "2_2") (pintype "input"))
      (node (ref "R15") (pin "1") (pinfunction "1_1") (pintype "input"))
      (node (ref "SW3") (pin "2") (pinfunction "2_2") (pintype "input"))
      (node (ref "U24") (pin "26") (pinfunction "RUN_26") (pintype "input"))
    )
    (net (code "66") (name "unconnected-(USBC1-SBU1-PadA8)") (class "Default")
      (node (ref "USBC1") (pin "A8") (pinfunction "SBU1_A8") (pintype "input+no_connect"))
    )
    (net (code "67") (name "unconnected-(USBC1-SBU2-PadB8)") (class "Default")
      (node (ref "USBC1") (pin "B8") (pinfunction "SBU2_B8") (pintype "input+no_connect"))
    )
  )
)
